# board.net
KiCad netlist of a schematic drawn in EAGLE
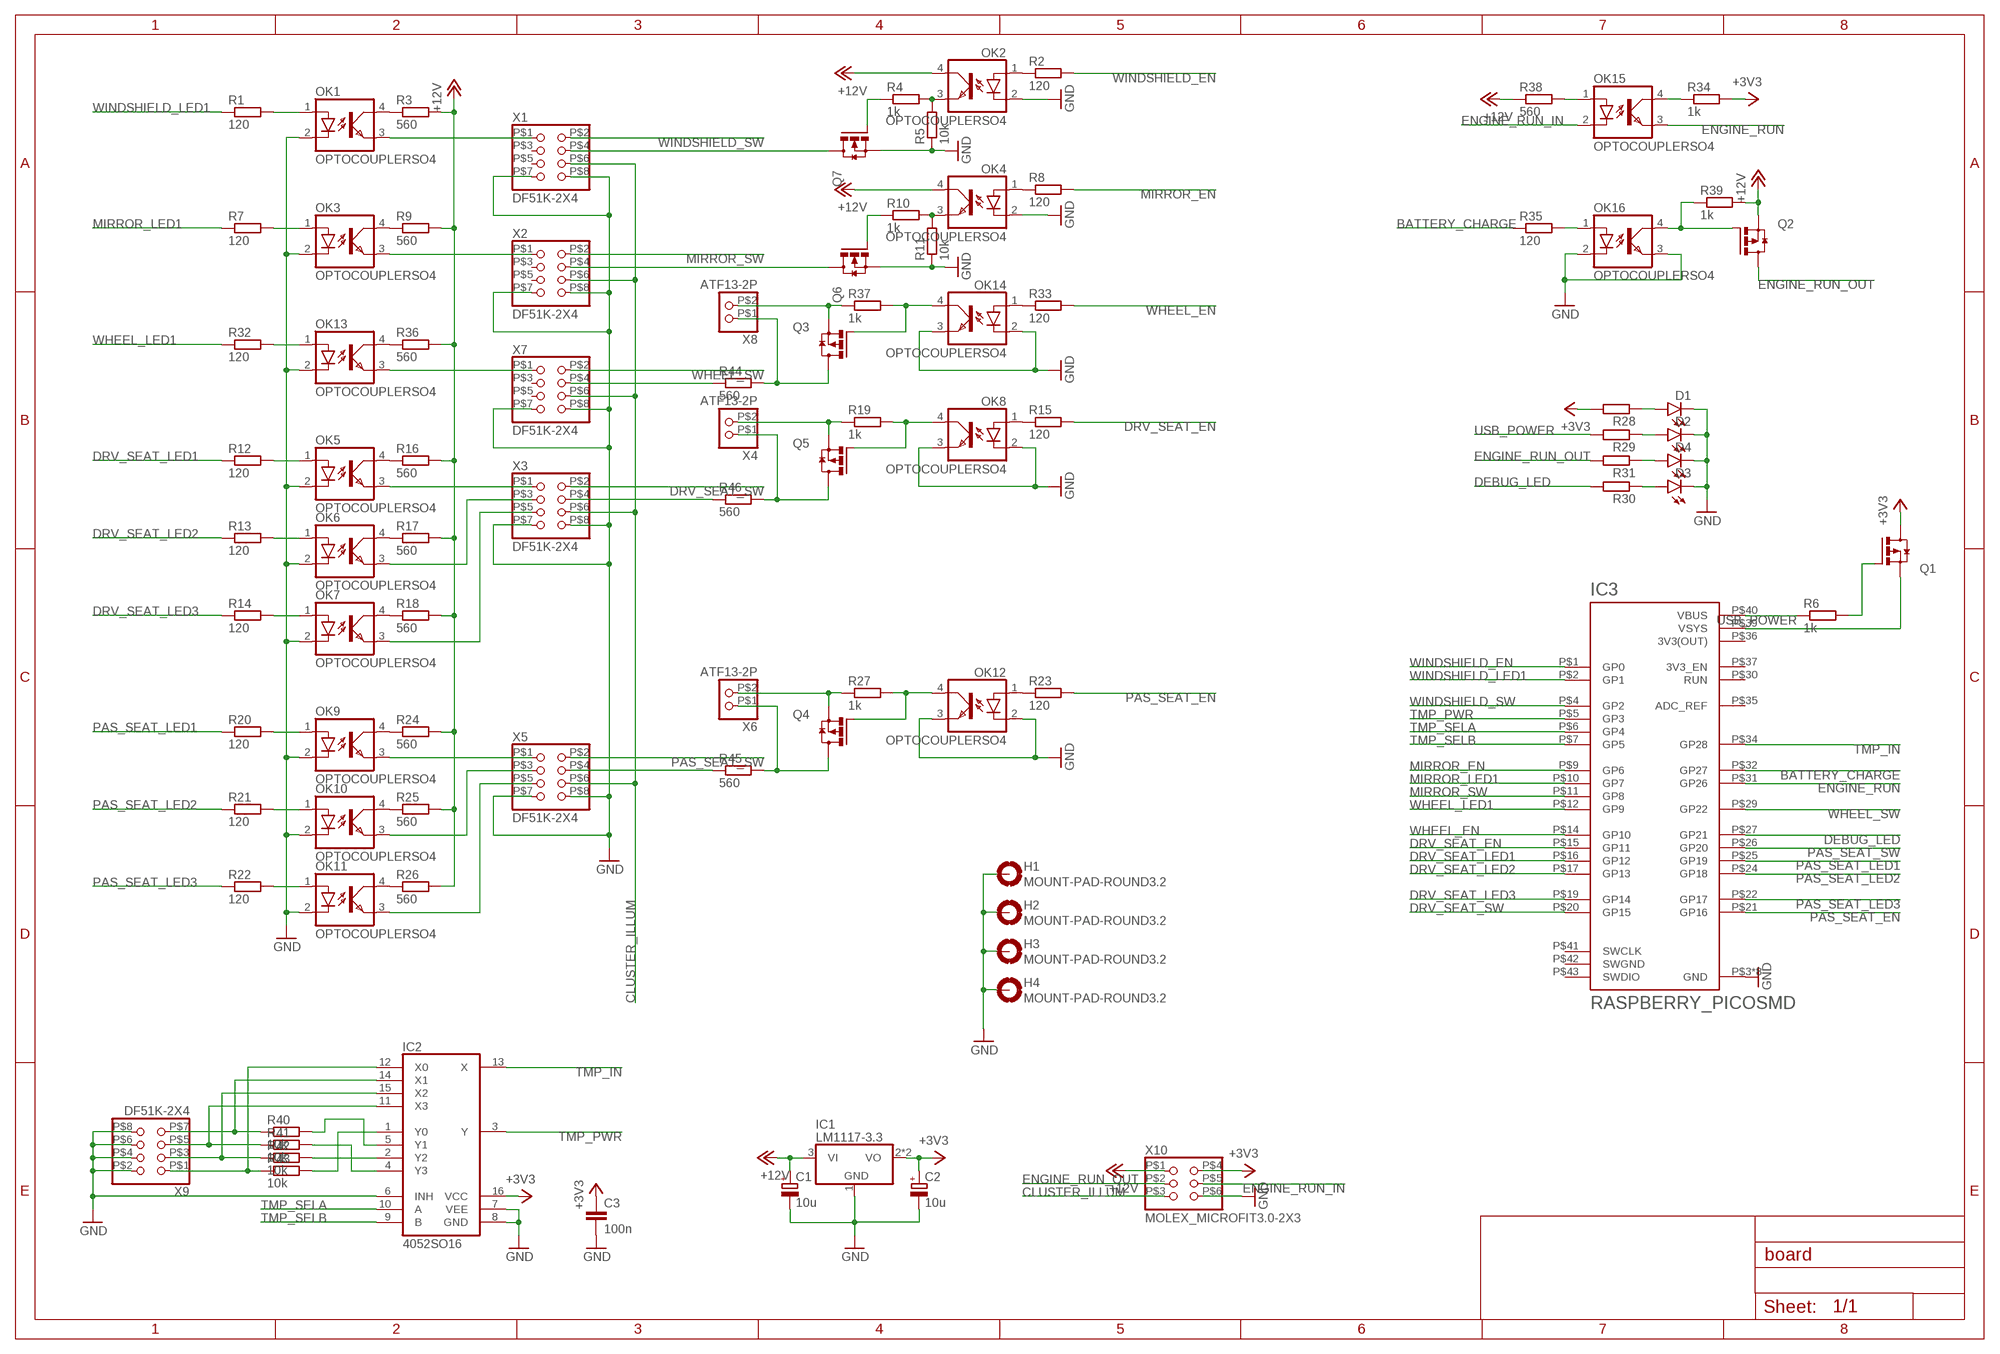
[diagram p0: schematic, sheet 1]

(export (version "E")
  (design (tool "Eeschema 10.0.6"))
  (components
    (comp (ref "C1")
      (value "10u")
      (footprint "eagle-import:C_4MM")
      (libsource (lib "eagle-import") (part "CAPACITOR_POL4MM^2"))
    )
    (comp (ref "C2")
      (value "10u")
      (footprint "eagle-import:C_4MM")
      (libsource (lib "eagle-import") (part "CAPACITOR_POL4MM^2"))
    )
    (comp (ref "C3")
      (value "100n")
      (footprint "eagle-import:C0805")
      (libsource (lib "eagle-import") (part "CAPACITOR0805"))
    )
    (comp (ref "D1")
      (value "LED1206")
      (footprint "eagle-import:CHIPLED_1206")
      (libsource (lib "eagle-import") (part "LED1206"))
    )
    (comp (ref "D2")
      (value "LED1206")
      (footprint "eagle-import:CHIPLED_1206")
      (libsource (lib "eagle-import") (part "LED1206"))
    )
    (comp (ref "D3")
      (value "LED1206")
      (footprint "eagle-import:CHIPLED_1206")
      (libsource (lib "eagle-import") (part "LED1206"))
    )
    (comp (ref "D4")
      (value "LED1206")
      (footprint "eagle-import:CHIPLED_1206")
      (libsource (lib "eagle-import") (part "LED1206"))
    )
    (comp (ref "H1")
      (value "MOUNT-PAD-ROUND3.2")
      (footprint "eagle-import:3,2-PAD")
      (libsource (lib "eagle-import") (part "MOUNT-PAD-ROUND3.2"))
    )
    (comp (ref "H2")
      (value "MOUNT-PAD-ROUND3.2")
      (footprint "eagle-import:3,2-PAD")
      (libsource (lib "eagle-import") (part "MOUNT-PAD-ROUND3.2"))
    )
    (comp (ref "H3")
      (value "MOUNT-PAD-ROUND3.2")
      (footprint "eagle-import:3,2-PAD")
      (libsource (lib "eagle-import") (part "MOUNT-PAD-ROUND3.2"))
    )
    (comp (ref "H4")
      (value "MOUNT-PAD-ROUND3.2")
      (footprint "eagle-import:3,2-PAD")
      (libsource (lib "eagle-import") (part "MOUNT-PAD-ROUND3.2"))
    )
    (comp (ref "IC1")
      (value "LM1117-3.3")
      (footprint "eagle-import:SOT223")
      (libsource (lib "eagle-import") (part "LM1117-3.3"))
    )
    (comp (ref "IC2")
      (value "4052SO16")
      (footprint "eagle-import:SO16")
      (libsource (lib "eagle-import") (part "4052SO16"))
    )
    (comp (ref "IC3")
      (value "RASPBERRY_PICOSMD")
      (footprint "eagle-import:PICO-PKG-SMD")
      (libsource (lib "eagle-import") (part "RASPBERRY_PICOSMD"))
    )
    (comp (ref "OK1")
      (value "OPTOCOUPLERSO4")
      (footprint "eagle-import:SO04")
      (libsource (lib "eagle-import") (part "OPTOCOUPLERSO4"))
    )
    (comp (ref "OK2")
      (value "OPTOCOUPLERSO4")
      (footprint "eagle-import:SO04")
      (libsource (lib "eagle-import") (part "OPTOCOUPLERSO4"))
    )
    (comp (ref "OK3")
      (value "OPTOCOUPLERSO4")
      (footprint "eagle-import:SO04")
      (libsource (lib "eagle-import") (part "OPTOCOUPLERSO4"))
    )
    (comp (ref "OK4")
      (value "OPTOCOUPLERSO4")
      (footprint "eagle-import:SO04")
      (libsource (lib "eagle-import") (part "OPTOCOUPLERSO4"))
    )
    (comp (ref "OK5")
      (value "OPTOCOUPLERSO4")
      (footprint "eagle-import:SO04")
      (libsource (lib "eagle-import") (part "OPTOCOUPLERSO4"))
    )
    (comp (ref "OK6")
      (value "OPTOCOUPLERSO4")
      (footprint "eagle-import:SO04")
      (libsource (lib "eagle-import") (part "OPTOCOUPLERSO4"))
    )
    (comp (ref "OK7")
      (value "OPTOCOUPLERSO4")
      (footprint "eagle-import:SO04")
      (libsource (lib "eagle-import") (part "OPTOCOUPLERSO4"))
    )
    (comp (ref "OK8")
      (value "OPTOCOUPLERSO4")
      (footprint "eagle-import:SO04")
      (libsource (lib "eagle-import") (part "OPTOCOUPLERSO4"))
    )
    (comp (ref "OK9")
      (value "OPTOCOUPLERSO4")
      (footprint "eagle-import:SO04")
      (libsource (lib "eagle-import") (part "OPTOCOUPLERSO4"))
    )
    (comp (ref "OK10")
      (value "OPTOCOUPLERSO4")
      (footprint "eagle-import:SO04")
      (libsource (lib "eagle-import") (part "OPTOCOUPLERSO4"))
    )
    (comp (ref "OK11")
      (value "OPTOCOUPLERSO4")
      (footprint "eagle-import:SO04")
      (libsource (lib "eagle-import") (part "OPTOCOUPLERSO4"))
    )
    (comp (ref "OK12")
      (value "OPTOCOUPLERSO4")
      (footprint "eagle-import:SO04")
      (libsource (lib "eagle-import") (part "OPTOCOUPLERSO4"))
    )
    (comp (ref "OK13")
      (value "OPTOCOUPLERSO4")
      (footprint "eagle-import:SO04")
      (libsource (lib "eagle-import") (part "OPTOCOUPLERSO4"))
    )
    (comp (ref "OK14")
      (value "OPTOCOUPLERSO4")
      (footprint "eagle-import:SO04")
      (libsource (lib "eagle-import") (part "OPTOCOUPLERSO4"))
    )
    (comp (ref "OK15")
      (value "OPTOCOUPLERSO4")
      (footprint "eagle-import:SO04")
      (libsource (lib "eagle-import") (part "OPTOCOUPLERSO4"))
    )
    (comp (ref "OK16")
      (value "OPTOCOUPLERSO4")
      (footprint "eagle-import:SO04")
      (libsource (lib "eagle-import") (part "OPTOCOUPLERSO4"))
    )
    (comp (ref "Q1")
      (value "MOSFET_P_CHANNELSOT23")
      (footprint "eagle-import:SOT23")
      (libsource (lib "eagle-import") (part "MOSFET_P_CHANNELSOT23"))
    )
    (comp (ref "Q2")
      (value "MOSFET_P_CHANNELSOT23")
      (footprint "eagle-import:SOT23")
      (libsource (lib "eagle-import") (part "MOSFET_P_CHANNELSOT23"))
    )
    (comp (ref "Q3")
      (value "MOSFET_P_CHANNELTO252")
      (footprint "eagle-import:TO252")
      (libsource (lib "eagle-import") (part "MOSFET_P_CHANNELTO252"))
    )
    (comp (ref "Q4")
      (value "MOSFET_P_CHANNELTO252")
      (footprint "eagle-import:TO252")
      (libsource (lib "eagle-import") (part "MOSFET_P_CHANNELTO252"))
    )
    (comp (ref "Q5")
      (value "MOSFET_P_CHANNELTO252")
      (footprint "eagle-import:TO252")
      (libsource (lib "eagle-import") (part "MOSFET_P_CHANNELTO252"))
    )
    (comp (ref "Q6")
      (value "MOSFET_N_CHANNELSOT23")
      (footprint "eagle-import:SOT23")
      (libsource (lib "eagle-import") (part "MOSFET_N_CHANNELSOT23"))
    )
    (comp (ref "Q7")
      (value "MOSFET_N_CHANNELSOT23")
      (footprint "eagle-import:SOT23")
      (libsource (lib "eagle-import") (part "MOSFET_N_CHANNELSOT23"))
    )
    (comp (ref "R1")
      (value "120")
      (footprint "eagle-import:R0805")
      (libsource (lib "eagle-import") (part "RESISTOR0805"))
    )
    (comp (ref "R2")
      (value "120")
      (footprint "eagle-import:R0805")
      (libsource (lib "eagle-import") (part "RESISTOR0805"))
    )
    (comp (ref "R3")
      (value "560")
      (footprint "eagle-import:R0805")
      (libsource (lib "eagle-import") (part "RESISTOR0805"))
    )
    (comp (ref "R4")
      (value "1k")
      (footprint "eagle-import:R0805")
      (libsource (lib "eagle-import") (part "RESISTOR0805"))
    )
    (comp (ref "R5")
      (value "10k")
      (footprint "eagle-import:R0805")
      (libsource (lib "eagle-import") (part "RESISTOR0805"))
    )
    (comp (ref "R6")
      (value "1k")
      (footprint "eagle-import:R0805")
      (libsource (lib "eagle-import") (part "RESISTOR0805"))
    )
    (comp (ref "R7")
      (value "120")
      (footprint "eagle-import:R0805")
      (libsource (lib "eagle-import") (part "RESISTOR0805"))
    )
    (comp (ref "R8")
      (value "120")
      (footprint "eagle-import:R0805")
      (libsource (lib "eagle-import") (part "RESISTOR0805"))
    )
    (comp (ref "R9")
      (value "560")
      (footprint "eagle-import:R0805")
      (libsource (lib "eagle-import") (part "RESISTOR0805"))
    )
    (comp (ref "R10")
      (value "1k")
      (footprint "eagle-import:R0805")
      (libsource (lib "eagle-import") (part "RESISTOR0805"))
    )
    (comp (ref "R11")
      (value "10k")
      (footprint "eagle-import:R0805")
      (libsource (lib "eagle-import") (part "RESISTOR0805"))
    )
    (comp (ref "R12")
      (value "120")
      (footprint "eagle-import:R0805")
      (libsource (lib "eagle-import") (part "RESISTOR0805"))
    )
    (comp (ref "R13")
      (value "120")
      (footprint "eagle-import:R0805")
      (libsource (lib "eagle-import") (part "RESISTOR0805"))
    )
    (comp (ref "R14")
      (value "120")
      (footprint "eagle-import:R0805")
      (libsource (lib "eagle-import") (part "RESISTOR0805"))
    )
    (comp (ref "R15")
      (value "120")
      (footprint "eagle-import:R0805")
      (libsource (lib "eagle-import") (part "RESISTOR0805"))
    )
    (comp (ref "R16")
      (value "560")
      (footprint "eagle-import:R0805")
      (libsource (lib "eagle-import") (part "RESISTOR0805"))
    )
    (comp (ref "R17")
      (value "560")
      (footprint "eagle-import:R0805")
      (libsource (lib "eagle-import") (part "RESISTOR0805"))
    )
    (comp (ref "R18")
      (value "560")
      (footprint "eagle-import:R0805")
      (libsource (lib "eagle-import") (part "RESISTOR0805"))
    )
    (comp (ref "R19")
      (value "1k")
      (footprint "eagle-import:R0805")
      (libsource (lib "eagle-import") (part "RESISTOR0805"))
    )
    (comp (ref "R20")
      (value "120")
      (footprint "eagle-import:R0805")
      (libsource (lib "eagle-import") (part "RESISTOR0805"))
    )
    (comp (ref "R21")
      (value "120")
      (footprint "eagle-import:R0805")
      (libsource (lib "eagle-import") (part "RESISTOR0805"))
    )
    (comp (ref "R22")
      (value "120")
      (footprint "eagle-import:R0805")
      (libsource (lib "eagle-import") (part "RESISTOR0805"))
    )
    (comp (ref "R23")
      (value "120")
      (footprint "eagle-import:R0805")
      (libsource (lib "eagle-import") (part "RESISTOR0805"))
    )
    (comp (ref "R24")
      (value "560")
      (footprint "eagle-import:R0805")
      (libsource (lib "eagle-import") (part "RESISTOR0805"))
    )
    (comp (ref "R25")
      (value "560")
      (footprint "eagle-import:R0805")
      (libsource (lib "eagle-import") (part "RESISTOR0805"))
    )
    (comp (ref "R26")
      (value "560")
      (footprint "eagle-import:R0805")
      (libsource (lib "eagle-import") (part "RESISTOR0805"))
    )
    (comp (ref "R27")
      (value "1k")
      (footprint "eagle-import:R0805")
      (libsource (lib "eagle-import") (part "RESISTOR0805"))
    )
    (comp (ref "R28")
      (value "RESISTOR0805")
      (footprint "eagle-import:R0805")
      (libsource (lib "eagle-import") (part "RESISTOR0805"))
    )
    (comp (ref "R29")
      (value "RESISTOR0805")
      (footprint "eagle-import:R0805")
      (libsource (lib "eagle-import") (part "RESISTOR0805"))
    )
    (comp (ref "R30")
      (value "RESISTOR0805")
      (footprint "eagle-import:R0805")
      (libsource (lib "eagle-import") (part "RESISTOR0805"))
    )
    (comp (ref "R31")
      (value "RESISTOR0805")
      (footprint "eagle-import:R0805")
      (libsource (lib "eagle-import") (part "RESISTOR0805"))
    )
    (comp (ref "R32")
      (value "120")
      (footprint "eagle-import:R0805")
      (libsource (lib "eagle-import") (part "RESISTOR0805"))
    )
    (comp (ref "R33")
      (value "120")
      (footprint "eagle-import:R0805")
      (libsource (lib "eagle-import") (part "RESISTOR0805"))
    )
    (comp (ref "R34")
      (value "1k")
      (footprint "eagle-import:R0805")
      (libsource (lib "eagle-import") (part "RESISTOR0805"))
    )
    (comp (ref "R35")
      (value "120")
      (footprint "eagle-import:R0805")
      (libsource (lib "eagle-import") (part "RESISTOR0805"))
    )
    (comp (ref "R36")
      (value "560")
      (footprint "eagle-import:R0805")
      (libsource (lib "eagle-import") (part "RESISTOR0805"))
    )
    (comp (ref "R37")
      (value "1k")
      (footprint "eagle-import:R0805")
      (libsource (lib "eagle-import") (part "RESISTOR0805"))
    )
    (comp (ref "R38")
      (value "560")
      (footprint "eagle-import:R0805")
      (libsource (lib "eagle-import") (part "RESISTOR0805"))
    )
    (comp (ref "R39")
      (value "1k")
      (footprint "eagle-import:R0805")
      (libsource (lib "eagle-import") (part "RESISTOR0805"))
    )
    (comp (ref "R40")
      (value "10k")
      (footprint "eagle-import:R0805")
      (libsource (lib "eagle-import") (part "RESISTOR0805"))
    )
    (comp (ref "R41")
      (value "10k")
      (footprint "eagle-import:R0805")
      (libsource (lib "eagle-import") (part "RESISTOR0805"))
    )
    (comp (ref "R42")
      (value "10k")
      (footprint "eagle-import:R0805")
      (libsource (lib "eagle-import") (part "RESISTOR0805"))
    )
    (comp (ref "R43")
      (value "10k")
      (footprint "eagle-import:R0805")
      (libsource (lib "eagle-import") (part "RESISTOR0805"))
    )
    (comp (ref "R44")
      (value "560")
      (footprint "eagle-import:R0805")
      (libsource (lib "eagle-import") (part "RESISTOR0805"))
    )
    (comp (ref "R45")
      (value "560")
      (footprint "eagle-import:R0805")
      (libsource (lib "eagle-import") (part "RESISTOR0805"))
    )
    (comp (ref "R46")
      (value "560")
      (footprint "eagle-import:R0805")
      (libsource (lib "eagle-import") (part "RESISTOR0805"))
    )
    (comp (ref "X1")
      (value "DF51K-2X4")
      (footprint "eagle-import:DF51K-2X4")
      (libsource (lib "eagle-import") (part "DF51K-2X4"))
    )
    (comp (ref "X2")
      (value "DF51K-2X4")
      (footprint "eagle-import:DF51K-2X4")
      (libsource (lib "eagle-import") (part "DF51K-2X4"))
    )
    (comp (ref "X3")
      (value "DF51K-2X4")
      (footprint "eagle-import:DF51K-2X4")
      (libsource (lib "eagle-import") (part "DF51K-2X4"))
    )
    (comp (ref "X4")
      (value "ATF13-2P")
      (footprint "eagle-import:ATF13-2P")
      (libsource (lib "eagle-import") (part "ATF13-2P"))
    )
    (comp (ref "X5")
      (value "DF51K-2X4")
      (footprint "eagle-import:DF51K-2X4")
      (libsource (lib "eagle-import") (part "DF51K-2X4"))
    )
    (comp (ref "X6")
      (value "ATF13-2P")
      (footprint "eagle-import:ATF13-2P")
      (libsource (lib "eagle-import") (part "ATF13-2P"))
    )
    (comp (ref "X7")
      (value "DF51K-2X4")
      (footprint "eagle-import:DF51K-2X4")
      (libsource (lib "eagle-import") (part "DF51K-2X4"))
    )
    (comp (ref "X8")
      (value "ATF13-2P")
      (footprint "eagle-import:ATF13-2P")
      (libsource (lib "eagle-import") (part "ATF13-2P"))
    )
    (comp (ref "X9")
      (value "DF51K-2X4")
      (footprint "eagle-import:DF51K-2X4")
      (libsource (lib "eagle-import") (part "DF51K-2X4"))
    )
    (comp (ref "X10")
      (value "MOLEX_MICROFIT3.0-2X3")
      (footprint "eagle-import:MOLEX_MICROFIT3.0-2X3")
      (libsource (lib "eagle-import") (part "MOLEX_MICROFIT3.0-2X3"))
    )
  )
  (nets
    (net (code "1") (name "+3V3") (class "Default")
      (node (ref "C2") (pin "+") (pinfunction "+_+") (pintype "passive"))
      (node (ref "C3") (pin "1") (pinfunction "1_1") (pintype "passive"))
      (node (ref "IC1") (pin "2") (pinfunction "VO_2") (pintype "passive"))
      (node (ref "IC1") (pin "4") (pinfunction "VO_4") (pintype "passive"))
      (node (ref "IC2") (pin "16") (pinfunction "VCC_16") (pintype "bidirectional"))
      (node (ref "Q1") (pin "3") (pinfunction "D_3") (pintype "passive"))
      (node (ref "R28") (pin "2") (pinfunction "2_2") (pintype "passive"))
      (node (ref "R34") (pin "2") (pinfunction "2_2") (pintype "passive"))
      (node (ref "X10") (pin "P$4") (pinfunction "2_P$4") (pintype "passive"))
    )
    (net (code "2") (name "+12V") (class "Default")
      (node (ref "C1") (pin "+") (pinfunction "+_+") (pintype "passive"))
      (node (ref "IC1") (pin "3") (pinfunction "VI_3") (pintype "input"))
      (node (ref "OK2") (pin "4") (pinfunction "COL_4") (pintype "passive"))
      (node (ref "OK4") (pin "4") (pinfunction "COL_4") (pintype "passive"))
      (node (ref "Q2") (pin "2") (pinfunction "S_2") (pintype "passive"))
      (node (ref "R16") (pin "2") (pinfunction "2_2") (pintype "passive"))
      (node (ref "R17") (pin "2") (pinfunction "2_2") (pintype "passive"))
      (node (ref "R18") (pin "2") (pinfunction "2_2") (pintype "passive"))
      (node (ref "R24") (pin "2") (pinfunction "2_2") (pintype "passive"))
      (node (ref "R25") (pin "2") (pinfunction "2_2") (pintype "passive"))
      (node (ref "R26") (pin "2") (pinfunction "2_2") (pintype "passive"))
      (node (ref "R3") (pin "2") (pinfunction "2_2") (pintype "passive"))
      (node (ref "R36") (pin "2") (pinfunction "2_2") (pintype "passive"))
      (node (ref "R38") (pin "1") (pinfunction "1_1") (pintype "passive"))
      (node (ref "R39") (pin "2") (pinfunction "2_2") (pintype "passive"))
      (node (ref "R9") (pin "2") (pinfunction "2_2") (pintype "passive"))
      (node (ref "X10") (pin "P$1") (pinfunction "1_P$1") (pintype "passive"))
    )
    (net (code "3") (name "/3V3(OUT)") (class "Default")
      (node (ref "IC3") (pin "P$36") (pinfunction "3V3(OUT)_P$36") (pintype "power_in"))
    )
    (net (code "4") (name "/BATTERY_CHARGE") (class "Default")
      (node (ref "IC3") (pin "P$32") (pinfunction "GP27_P$32") (pintype "bidirectional"))
      (node (ref "R35") (pin "1") (pinfunction "1_1") (pintype "passive"))
    )
    (net (code "5") (name "/CLUSTER_ILLUM") (class "Default")
      (node (ref "X1") (pin "P$6") (pinfunction "6_P$6") (pintype "passive"))
      (node (ref "X10") (pin "P$3") (pinfunction "5_P$3") (pintype "passive"))
      (node (ref "X2") (pin "P$6") (pinfunction "6_P$6") (pintype "passive"))
      (node (ref "X3") (pin "P$6") (pinfunction "6_P$6") (pintype "passive"))
      (node (ref "X5") (pin "P$6") (pinfunction "6_P$6") (pintype "passive"))
      (node (ref "X7") (pin "P$6") (pinfunction "6_P$6") (pintype "passive"))
    )
    (net (code "6") (name "/DEBUG_LED") (class "Default")
      (node (ref "IC3") (pin "P$27") (pinfunction "GP21_P$27") (pintype "bidirectional"))
      (node (ref "R30") (pin "2") (pinfunction "2_2") (pintype "passive"))
    )
    (net (code "7") (name "/DRV_SEAT_EN") (class "Default")
      (node (ref "IC3") (pin "P$15") (pinfunction "GP11_P$15") (pintype "bidirectional"))
      (node (ref "R15") (pin "2") (pinfunction "2_2") (pintype "passive"))
    )
    (net (code "8") (name "/DRV_SEAT_LED1") (class "Default")
      (node (ref "IC3") (pin "P$16") (pinfunction "GP12_P$16") (pintype "bidirectional"))
      (node (ref "R12") (pin "1") (pinfunction "1_1") (pintype "passive"))
    )
    (net (code "9") (name "/DRV_SEAT_LED2") (class "Default")
      (node (ref "IC3") (pin "P$17") (pinfunction "GP13_P$17") (pintype "bidirectional"))
      (node (ref "R13") (pin "1") (pinfunction "1_1") (pintype "passive"))
    )
    (net (code "10") (name "/DRV_SEAT_LED3") (class "Default")
      (node (ref "IC3") (pin "P$19") (pinfunction "GP14_P$19") (pintype "bidirectional"))
      (node (ref "R14") (pin "1") (pinfunction "1_1") (pintype "passive"))
    )
    (net (code "11") (name "/DRV_SEAT_SW") (class "Default")
      (node (ref "IC3") (pin "P$20") (pinfunction "GP15_P$20") (pintype "bidirectional"))
      (node (ref "X3") (pin "P$2") (pinfunction "2_P$2") (pintype "passive"))
    )
    (net (code "12") (name "/ENGINE_RUN") (class "Default")
      (node (ref "IC3") (pin "P$31") (pinfunction "GP26_P$31") (pintype "bidirectional"))
      (node (ref "OK15") (pin "3") (pinfunction "EMIT_3") (pintype "passive"))
    )
    (net (code "13") (name "/ENGINE_RUN_IN") (class "Default")
      (node (ref "OK15") (pin "2") (pinfunction "C_2") (pintype "passive"))
      (node (ref "X10") (pin "P$5") (pinfunction "4_P$5") (pintype "passive"))
    )
    (net (code "14") (name "/ENGINE_RUN_OUT") (class "Default")
      (node (ref "Q2") (pin "3") (pinfunction "D_3") (pintype "passive"))
      (node (ref "R31") (pin "2") (pinfunction "2_2") (pintype "passive"))
      (node (ref "X10") (pin "P$2") (pinfunction "3_P$2") (pintype "passive"))
    )
    (net (code "15") (name "/MIRROR_EN") (class "Default")
      (node (ref "IC3") (pin "P$9") (pinfunction "GP6_P$9") (pintype "bidirectional"))
      (node (ref "R8") (pin "2") (pinfunction "2_2") (pintype "passive"))
    )
    (net (code "16") (name "/MIRROR_LED1") (class "Default")
      (node (ref "IC3") (pin "P$10") (pinfunction "GP7_P$10") (pintype "bidirectional"))
      (node (ref "R7") (pin "1") (pinfunction "1_1") (pintype "passive"))
    )
    (net (code "17") (name "/MIRROR_SW") (class "Default")
      (node (ref "IC3") (pin "P$11") (pinfunction "GP8_P$11") (pintype "bidirectional"))
      (node (ref "X2") (pin "P$2") (pinfunction "2_P$2") (pintype "passive"))
    )
    (net (code "18") (name "/PAS_SEAT_EN") (class "Default")
      (node (ref "IC3") (pin "P$21") (pinfunction "GP16_P$21") (pintype "bidirectional"))
      (node (ref "R23") (pin "2") (pinfunction "2_2") (pintype "passive"))
    )
    (net (code "19") (name "/PAS_SEAT_LED1") (class "Default")
      (node (ref "IC3") (pin "P$25") (pinfunction "GP19_P$25") (pintype "bidirectional"))
      (node (ref "R20") (pin "1") (pinfunction "1_1") (pintype "passive"))
    )
    (net (code "20") (name "/PAS_SEAT_LED2") (class "Default")
      (node (ref "IC3") (pin "P$24") (pinfunction "GP18_P$24") (pintype "bidirectional"))
      (node (ref "R21") (pin "1") (pinfunction "1_1") (pintype "passive"))
    )
    (net (code "21") (name "/PAS_SEAT_LED3") (class "Default")
      (node (ref "IC3") (pin "P$22") (pinfunction "GP17_P$22") (pintype "bidirectional"))
      (node (ref "R22") (pin "1") (pinfunction "1_1") (pintype "passive"))
    )
    (net (code "22") (name "/PAS_SEAT_SW") (class "Default")
      (node (ref "IC3") (pin "P$26") (pinfunction "GP20_P$26") (pintype "bidirectional"))
      (node (ref "X5") (pin "P$2") (pinfunction "2_P$2") (pintype "passive"))
    )
    (net (code "23") (name "/SWGND") (class "Default")
      (node (ref "IC3") (pin "P$42") (pinfunction "SWGND_P$42") (pintype "power_in"))
    )
    (net (code "24") (name "/TMP_IN") (class "Default")
      (node (ref "IC2") (pin "13") (pinfunction "X_13") (pintype "bidirectional"))
      (node (ref "IC3") (pin "P$34") (pinfunction "GP28_P$34") (pintype "bidirectional"))
    )
    (net (code "25") (name "/TMP_PWR") (class "Default")
      (node (ref "IC2") (pin "3") (pinfunction "Y_3") (pintype "bidirectional"))
      (node (ref "IC3") (pin "P$5") (pinfunction "GP3_P$5") (pintype "bidirectional"))
    )
    (net (code "26") (name "/TMP_SELA") (class "Default")
      (node (ref "IC2") (pin "10") (pinfunction "A_10") (pintype "input"))
      (node (ref "IC3") (pin "P$6") (pinfunction "GP4_P$6") (pintype "bidirectional"))
    )
    (net (code "27") (name "/TMP_SELB") (class "Default")
      (node (ref "IC2") (pin "9") (pinfunction "B_9") (pintype "input"))
      (node (ref "IC3") (pin "P$7") (pinfunction "GP5_P$7") (pintype "bidirectional"))
    )
    (net (code "28") (name "/USB_POWER") (class "Default")
      (node (ref "IC3") (pin "P$40") (pinfunction "VBUS_P$40") (pintype "power_in"))
      (node (ref "R29") (pin "2") (pinfunction "2_2") (pintype "passive"))
      (node (ref "R6") (pin "1") (pinfunction "1_1") (pintype "passive"))
    )
    (net (code "29") (name "/WHEEL_EN") (class "Default")
      (node (ref "IC3") (pin "P$14") (pinfunction "GP10_P$14") (pintype "bidirectional"))
      (node (ref "R33") (pin "2") (pinfunction "2_2") (pintype "passive"))
    )
    (net (code "30") (name "/WHEEL_LED1") (class "Default")
      (node (ref "IC3") (pin "P$12") (pinfunction "GP9_P$12") (pintype "bidirectional"))
      (node (ref "R32") (pin "1") (pinfunction "1_1") (pintype "passive"))
    )
    (net (code "31") (name "/WHEEL_SW") (class "Default")
      (node (ref "IC3") (pin "P$29") (pinfunction "GP22_P$29") (pintype "bidirectional"))
      (node (ref "X7") (pin "P$2") (pinfunction "2_P$2") (pintype "passive"))
    )
    (net (code "32") (name "/WINDSHIELD_EN") (class "Default")
      (node (ref "IC3") (pin "P$1") (pinfunction "GP0_P$1") (pintype "bidirectional"))
      (node (ref "R2") (pin "2") (pinfunction "2_2") (pintype "passive"))
    )
    (net (code "33") (name "/WINDSHIELD_LED1") (class "Default")
      (node (ref "IC3") (pin "P$2") (pinfunction "GP1_P$2") (pintype "bidirectional"))
      (node (ref "R1") (pin "1") (pinfunction "1_1") (pintype "passive"))
    )
    (net (code "34") (name "/WINDSHIELD_SW") (class "Default")
      (node (ref "IC3") (pin "P$4") (pinfunction "GP2_P$4") (pintype "bidirectional"))
      (node (ref "X1") (pin "P$2") (pinfunction "2_P$2") (pintype "passive"))
    )
    (net (code "35") (name "GND") (class "Default")
      (node (ref "C1") (pin "-") (pinfunction "-_-") (pintype "passive"))
      (node (ref "C2") (pin "-") (pinfunction "-_-") (pintype "passive"))
      (node (ref "C3") (pin "2") (pinfunction "2_2") (pintype "passive"))
      (node (ref "D1") (pin "C") (pinfunction "C_C") (pintype "passive"))
      (node (ref "D2") (pin "C") (pinfunction "C_C") (pintype "passive"))
      (node (ref "D3") (pin "C") (pinfunction "C_C") (pintype "passive"))
      (node (ref "D4") (pin "C") (pinfunction "C_C") (pintype "passive"))
      (node (ref "H1") (pin "B3,2") (pinfunction "MOUNT_B3,2") (pintype "passive"))
      (node (ref "H1") (pin "P$1") (pinfunction "MOUNT_P$1") (pintype "passive"))
      (node (ref "H1") (pin "P$2") (pinfunction "MOUNT_P$2") (pintype "passive"))
      (node (ref "H1") (pin "P$3") (pinfunction "MOUNT_P$3") (pintype "passive"))
      (node (ref "H1") (pin "P$4") (pinfunction "MOUNT_P$4") (pintype "passive"))
      (node (ref "H1") (pin "P$5") (pinfunction "MOUNT_P$5") (pintype "passive"))
      (node (ref "H1") (pin "P$6") (pinfunction "MOUNT_P$6") (pintype "passive"))
      (node (ref "H1") (pin "P$7") (pinfunction "MOUNT_P$7") (pintype "passive"))
      (node (ref "H1") (pin "P$8") (pinfunction "MOUNT_P$8") (pintype "passive"))
      (node (ref "H2") (pin "B3,2") (pinfunction "MOUNT_B3,2") (pintype "passive"))
      (node (ref "H2") (pin "P$1") (pinfunction "MOUNT_P$1") (pintype "passive"))
      (node (ref "H2") (pin "P$2") (pinfunction "MOUNT_P$2") (pintype "passive"))
      (node (ref "H2") (pin "P$3") (pinfunction "MOUNT_P$3") (pintype "passive"))
      (node (ref "H2") (pin "P$4") (pinfunction "MOUNT_P$4") (pintype "passive"))
      (node (ref "H2") (pin "P$5") (pinfunction "MOUNT_P$5") (pintype "passive"))
      (node (ref "H2") (pin "P$6") (pinfunction "MOUNT_P$6") (pintype "passive"))
      (node (ref "H2") (pin "P$7") (pinfunction "MOUNT_P$7") (pintype "passive"))
      (node (ref "H2") (pin "P$8") (pinfunction "MOUNT_P$8") (pintype "passive"))
      (node (ref "H3") (pin "B3,2") (pinfunction "MOUNT_B3,2") (pintype "passive"))
      (node (ref "H3") (pin "P$1") (pinfunction "MOUNT_P$1") (pintype "passive"))
      (node (ref "H3") (pin "P$2") (pinfunction "MOUNT_P$2") (pintype "passive"))
      (node (ref "H3") (pin "P$3") (pinfunction "MOUNT_P$3") (pintype "passive"))
      (node (ref "H3") (pin "P$4") (pinfunction "MOUNT_P$4") (pintype "passive"))
      (node (ref "H3") (pin "P$5") (pinfunction "MOUNT_P$5") (pintype "passive"))
      (node (ref "H3") (pin "P$6") (pinfunction "MOUNT_P$6") (pintype "passive"))
      (node (ref "H3") (pin "P$7") (pinfunction "MOUNT_P$7") (pintype "passive"))
      (node (ref "H3") (pin "P$8") (pinfunction "MOUNT_P$8") (pintype "passive"))
      (node (ref "H4") (pin "B3,2") (pinfunction "MOUNT_B3,2") (pintype "passive"))
      (node (ref "H4") (pin "P$1") (pinfunction "MOUNT_P$1") (pintype "passive"))
      (node (ref "H4") (pin "P$2") (pinfunction "MOUNT_P$2") (pintype "passive"))
      (node (ref "H4") (pin "P$3") (pinfunction "MOUNT_P$3") (pintype "passive"))
      (node (ref "H4") (pin "P$4") (pinfunction "MOUNT_P$4") (pintype "passive"))
      (node (ref "H4") (pin "P$5") (pinfunction "MOUNT_P$5") (pintype "passive"))
      (node (ref "H4") (pin "P$6") (pinfunction "MOUNT_P$6") (pintype "passive"))
      (node (ref "H4") (pin "P$7") (pinfunction "MOUNT_P$7") (pintype "passive"))
      (node (ref "H4") (pin "P$8") (pinfunction "MOUNT_P$8") (pintype "passive"))
      (node (ref "IC1") (pin "1") (pinfunction "GND_1") (pintype "passive"))
      (node (ref "IC2") (pin "6") (pinfunction "INH_6") (pintype "input"))
      (node (ref "IC2") (pin "7") (pinfunction "VEE_7") (pintype "bidirectional"))
      (node (ref "IC2") (pin "8") (pinfunction "GND_8") (pintype "bidirectional"))
      (node (ref "IC3") (pin "P$13") (pinfunction "GND_P$13") (pintype "power_in"))
      (node (ref "IC3") (pin "P$18") (pinfunction "GND_P$18") (pintype "power_in"))
      (node (ref "IC3") (pin "P$23") (pinfunction "GND_P$23") (pintype "power_in"))
      (node (ref "IC3") (pin "P$28") (pinfunction "GND_P$28") (pintype "power_in"))
      (node (ref "IC3") (pin "P$3") (pinfunction "GND_P$3") (pintype "power_in"))
      (node (ref "IC3") (pin "P$33") (pinfunction "GND_P$33") (pintype "power_in"))
      (node (ref "IC3") (pin "P$38") (pinfunction "GND_P$38") (pintype "power_in"))
      (node (ref "IC3") (pin "P$8") (pinfunction "GND_P$8") (pintype "power_in"))
      (node (ref "OK1") (pin "2") (pinfunction "C_2") (pintype "passive"))
      (node (ref "OK10") (pin "2") (pinfunction "C_2") (pintype "passive"))
      (node (ref "OK11") (pin "2") (pinfunction "C_2") (pintype "passive"))
      (node (ref "OK12") (pin "2") (pinfunction "C_2") (pintype "passive"))
      (node (ref "OK12") (pin "3") (pinfunction "EMIT_3") (pintype "passive"))
      (node (ref "OK13") (pin "2") (pinfunction "C_2") (pintype "passive"))
      (node (ref "OK14") (pin "2") (pinfunction "C_2") (pintype "passive"))
      (node (ref "OK14") (pin "3") (pinfunction "EMIT_3") (pintype "passive"))
      (node (ref "OK16") (pin "2") (pinfunction "C_2") (pintype "passive"))
      (node (ref "OK16") (pin "3") (pinfunction "EMIT_3") (pintype "passive"))
      (node (ref "OK2") (pin "2") (pinfunction "C_2") (pintype "passive"))
      (node (ref "OK3") (pin "2") (pinfunction "C_2") (pintype "passive"))
      (node (ref "OK4") (pin "2") (pinfunction "C_2") (pintype "passive"))
      (node (ref "OK5") (pin "2") (pinfunction "C_2") (pintype "passive"))
      (node (ref "OK6") (pin "2") (pinfunction "C_2") (pintype "passive"))
      (node (ref "OK7") (pin "2") (pinfunction "C_2") (pintype "passive"))
      (node (ref "OK8") (pin "2") (pinfunction "C_2") (pintype "passive"))
      (node (ref "OK8") (pin "3") (pinfunction "EMIT_3") (pintype "passive"))
      (node (ref "OK9") (pin "2") (pinfunction "C_2") (pintype "passive"))
      (node (ref "Q6") (pin "2") (pinfunction "S_2") (pintype "passive"))
      (node (ref "Q7") (pin "2") (pinfunction "S_2") (pintype "passive"))
      (node (ref "R11") (pin "1") (pinfunction "1_1") (pintype "passive"))
      (node (ref "R5") (pin "1") (pinfunction "1_1") (pintype "passive"))
      (node (ref "X1") (pin "P$7") (pinfunction "7_P$7") (pintype "passive"))
      (node (ref "X1") (pin "P$8") (pinfunction "8_P$8") (pintype "passive"))
      (node (ref "X10") (pin "P$6") (pinfunction "6_P$6") (pintype "passive"))
      (node (ref "X2") (pin "P$7") (pinfunction "7_P$7") (pintype "passive"))
      (node (ref "X2") (pin "P$8") (pinfunction "8_P$8") (pintype "passive"))
      (node (ref "X3") (pin "P$7") (pinfunction "7_P$7") (pintype "passive"))
      (node (ref "X3") (pin "P$8") (pinfunction "8_P$8") (pintype "passive"))
      (node (ref "X5") (pin "P$7") (pinfunction "7_P$7") (pintype "passive"))
      (node (ref "X5") (pin "P$8") (pinfunction "8_P$8") (pintype "passive"))
      (node (ref "X7") (pin "P$7") (pinfunction "7_P$7") (pintype "passive"))
      (node (ref "X7") (pin "P$8") (pinfunction "8_P$8") (pintype "passive"))
      (node (ref "X9") (pin "P$2") (pinfunction "2_P$2") (pintype "passive"))
      (node (ref "X9") (pin "P$4") (pinfunction "4_P$4") (pintype "passive"))
      (node (ref "X9") (pin "P$6") (pinfunction "6_P$6") (pintype "passive"))
      (node (ref "X9") (pin "P$8") (pinfunction "8_P$8") (pintype "passive"))
    )
    (net (code "36") (name "Net-(D1-PadA)") (class "Default")
      (node (ref "D1") (pin "A") (pinfunction "A_A") (pintype "passive"))
      (node (ref "R28") (pin "1") (pinfunction "1_1") (pintype "passive"))
    )
    (net (code "37") (name "Net-(D2-PadA)") (class "Default")
      (node (ref "D2") (pin "A") (pinfunction "A_A") (pintype "passive"))
      (node (ref "R29") (pin "1") (pinfunction "1_1") (pintype "passive"))
    )
    (net (code "38") (name "Net-(D3-PadA)") (class "Default")
      (node (ref "D3") (pin "A") (pinfunction "A_A") (pintype "passive"))
      (node (ref "R30") (pin "1") (pinfunction "1_1") (pintype "passive"))
    )
    (net (code "39") (name "Net-(D4-PadA)") (class "Default")
      (node (ref "D4") (pin "A") (pinfunction "A_A") (pintype "passive"))
      (node (ref "R31") (pin "1") (pinfunction "1_1") (pintype "passive"))
    )
    (net (code "40") (name "Net-(IC2-X0)") (class "Default")
      (node (ref "IC2") (pin "12") (pinfunction "X0_12") (pintype "bidirectional"))
      (node (ref "R43") (pin "1") (pinfunction "1_1") (pintype "passive"))
      (node (ref "X9") (pin "P$1") (pinfunction "1_P$1") (pintype "passive"))
    )
    (net (code "41") (name "Net-(IC2-X1)") (class "Default")
      (node (ref "IC2") (pin "14") (pinfunction "X1_14") (pintype "bidirectional"))
      (node (ref "R40") (pin "1") (pinfunction "1_1") (pintype "passive"))
      (node (ref "X9") (pin "P$7") (pinfunction "7_P$7") (pintype "passive"))
    )
    (net (code "42") (name "Net-(IC2-X2)") (class "Default")
      (node (ref "IC2") (pin "15") (pinfunction "X2_15") (pintype "bidirectional"))
      (node (ref "R42") (pin "1") (pinfunction "1_1") (pintype "passive"))
      (node (ref "X9") (pin "P$3") (pinfunction "3_P$3") (pintype "passive"))
    )
    (net (code "43") (name "Net-(IC2-X3)") (class "Default")
      (node (ref "IC2") (pin "11") (pinfunction "X3_11") (pintype "bidirectional"))
      (node (ref "R41") (pin "1") (pinfunction "1_1") (pintype "passive"))
      (node (ref "X9") (pin "P$5") (pinfunction "5_P$5") (pintype "passive"))
    )
    (net (code "44") (name "Net-(IC2-Y0)") (class "Default")
      (node (ref "IC2") (pin "1") (pinfunction "Y0_1") (pintype "bidirectional"))
      (node (ref "R43") (pin "2") (pinfunction "2_2") (pintype "passive"))
    )
    (net (code "45") (name "Net-(IC2-Y1)") (class "Default")
      (node (ref "IC2") (pin "5") (pinfunction "Y1_5") (pintype "bidirectional"))
      (node (ref "R40") (pin "2") (pinfunction "2_2") (pintype "passive"))
    )
    (net (code "46") (name "Net-(IC2-Y2)") (class "Default")
      (node (ref "IC2") (pin "2") (pinfunction "Y2_2") (pintype "bidirectional"))
      (node (ref "R42") (pin "2") (pinfunction "2_2") (pintype "passive"))
    )
    (net (code "47") (name "Net-(IC2-Y3)") (class "Default")
      (node (ref "IC2") (pin "4") (pinfunction "Y3_4") (pintype "bidirectional"))
      (node (ref "R41") (pin "2") (pinfunction "2_2") (pintype "passive"))
    )
    (net (code "48") (name "Net-(IC3-VSYS)") (class "Default")
      (node (ref "IC3") (pin "P$39") (pinfunction "VSYS_P$39") (pintype "power_in"))
      (node (ref "Q1") (pin "2") (pinfunction "S_2") (pintype "passive"))
    )
    (net (code "49") (name "Net-(OK1-A)") (class "Default")
      (node (ref "OK1") (pin "1") (pinfunction "A_1") (pintype "passive"))
      (node (ref "R1") (pin "2") (pinfunction "2_2") (pintype "passive"))
    )
    (net (code "50") (name "Net-(OK1-COL)") (class "Default")
      (node (ref "OK1") (pin "4") (pinfunction "COL_4") (pintype "passive"))
      (node (ref "R3") (pin "1") (pinfunction "1_1") (pintype "passive"))
    )
    (net (code "51") (name "Net-(OK1-EMIT)") (class "Default")
      (node (ref "OK1") (pin "3") (pinfunction "EMIT_3") (pintype "passive"))
      (node (ref "X1") (pin "P$1") (pinfunction "1_P$1") (pintype "passive"))
    )
    (net (code "52") (name "Net-(OK2-A)") (class "Default")
      (node (ref "OK2") (pin "1") (pinfunction "A_1") (pintype "passive"))
      (node (ref "R2") (pin "1") (pinfunction "1_1") (pintype "passive"))
    )
    (net (code "53") (name "Net-(OK2-EMIT)") (class "Default")
      (node (ref "OK2") (pin "3") (pinfunction "EMIT_3") (pintype "passive"))
      (node (ref "R4") (pin "2") (pinfunction "2_2") (pintype "passive"))
      (node (ref "R5") (pin "2") (pinfunction "2_2") (pintype "passive"))
    )
    (net (code "54") (name "Net-(OK3-A)") (class "Default")
      (node (ref "OK3") (pin "1") (pinfunction "A_1") (pintype "passive"))
      (node (ref "R7") (pin "2") (pinfunction "2_2") (pintype "passive"))
    )
    (net (code "55") (name "Net-(OK3-COL)") (class "Default")
      (node (ref "OK3") (pin "4") (pinfunction "COL_4") (pintype "passive"))
      (node (ref "R9") (pin "1") (pinfunction "1_1") (pintype "passive"))
    )
    (net (code "56") (name "Net-(OK3-EMIT)") (class "Default")
      (node (ref "OK3") (pin "3") (pinfunction "EMIT_3") (pintype "passive"))
      (node (ref "X2") (pin "P$1") (pinfunction "1_P$1") (pintype "passive"))
    )
    (net (code "57") (name "Net-(OK4-A)") (class "Default")
      (node (ref "OK4") (pin "1") (pinfunction "A_1") (pintype "passive"))
      (node (ref "R8") (pin "1") (pinfunction "1_1") (pintype "passive"))
    )
    (net (code "58") (name "Net-(OK4-EMIT)") (class "Default")
      (node (ref "OK4") (pin "3") (pinfunction "EMIT_3") (pintype "passive"))
      (node (ref "R10") (pin "2") (pinfunction "2_2") (pintype "passive"))
      (node (ref "R11") (pin "2") (pinfunction "2_2") (pintype "passive"))
    )
    (net (code "59") (name "Net-(OK5-A)") (class "Default")
      (node (ref "OK5") (pin "1") (pinfunction "A_1") (pintype "passive"))
      (node (ref "R12") (pin "2") (pinfunction "2_2") (pintype "passive"))
    )
    (net (code "60") (name "Net-(OK5-COL)") (class "Default")
      (node (ref "OK5") (pin "4") (pinfunction "COL_4") (pintype "passive"))
      (node (ref "R16") (pin "1") (pinfunction "1_1") (pintype "passive"))
    )
    (net (code "61") (name "Net-(OK5-EMIT)") (class "Default")
      (node (ref "OK5") (pin "3") (pinfunction "EMIT_3") (pintype "passive"))
      (node (ref "X3") (pin "P$1") (pinfunction "1_P$1") (pintype "passive"))
    )
    (net (code "62") (name "Net-(OK6-A)") (class "Default")
      (node (ref "OK6") (pin "1") (pinfunction "A_1") (pintype "passive"))
      (node (ref "R13") (pin "2") (pinfunction "2_2") (pintype "passive"))
    )
    (net (code "63") (name "Net-(OK6-COL)") (class "Default")
      (node (ref "OK6") (pin "4") (pinfunction "COL_4") (pintype "passive"))
      (node (ref "R17") (pin "1") (pinfunction "1_1") (pintype "passive"))
    )
    (net (code "64") (name "Net-(OK6-EMIT)") (class "Default")
      (node (ref "OK6") (pin "3") (pinfunction "EMIT_3") (pintype "passive"))
      (node (ref "X3") (pin "P$3") (pinfunction "3_P$3") (pintype "passive"))
    )
    (net (code "65") (name "Net-(OK7-A)") (class "Default")
      (node (ref "OK7") (pin "1") (pinfunction "A_1") (pintype "passive"))
      (node (ref "R14") (pin "2") (pinfunction "2_2") (pintype "passive"))
    )
    (net (code "66") (name "Net-(OK7-COL)") (class "Default")
      (node (ref "OK7") (pin "4") (pinfunction "COL_4") (pintype "passive"))
      (node (ref "R18") (pin "1") (pinfunction "1_1") (pintype "passive"))
    )
    (net (code "67") (name "Net-(OK7-EMIT)") (class "Default")
      (node (ref "OK7") (pin "3") (pinfunction "EMIT_3") (pintype "passive"))
      (node (ref "X3") (pin "P$5") (pinfunction "5_P$5") (pintype "passive"))
    )
    (net (code "68") (name "Net-(OK8-A)") (class "Default")
      (node (ref "OK8") (pin "1") (pinfunction "A_1") (pintype "passive"))
      (node (ref "R15") (pin "1") (pinfunction "1_1") (pintype "passive"))
    )
    (net (code "69") (name "Net-(OK8-COL)") (class "Default")
      (node (ref "OK8") (pin "4") (pinfunction "COL_4") (pintype "passive"))
      (node (ref "Q5") (pin "1") (pinfunction "G_1") (pintype "passive"))
      (node (ref "R19") (pin "2") (pinfunction "2_2") (pintype "passive"))
    )
    (net (code "70") (name "Net-(OK9-A)") (class "Default")
      (node (ref "OK9") (pin "1") (pinfunction "A_1") (pintype "passive"))
      (node (ref "R20") (pin "2") (pinfunction "2_2") (pintype "passive"))
    )
    (net (code "71") (name "Net-(OK9-COL)") (class "Default")
      (node (ref "OK9") (pin "4") (pinfunction "COL_4") (pintype "passive"))
      (node (ref "R24") (pin "1") (pinfunction "1_1") (pintype "passive"))
    )
    (net (code "72") (name "Net-(OK9-EMIT)") (class "Default")
      (node (ref "OK9") (pin "3") (pinfunction "EMIT_3") (pintype "passive"))
      (node (ref "X5") (pin "P$1") (pinfunction "1_P$1") (pintype "passive"))
    )
    (net (code "73") (name "Net-(OK10-A)") (class "Default")
      (node (ref "OK10") (pin "1") (pinfunction "A_1") (pintype "passive"))
      (node (ref "R21") (pin "2") (pinfunction "2_2") (pintype "passive"))
    )
    (net (code "74") (name "Net-(OK10-COL)") (class "Default")
      (node (ref "OK10") (pin "4") (pinfunction "COL_4") (pintype "passive"))
      (node (ref "R25") (pin "1") (pinfunction "1_1") (pintype "passive"))
    )
    (net (code "75") (name "Net-(OK10-EMIT)") (class "Default")
      (node (ref "OK10") (pin "3") (pinfunction "EMIT_3") (pintype "passive"))
      (node (ref "X5") (pin "P$3") (pinfunction "3_P$3") (pintype "passive"))
    )
    (net (code "76") (name "Net-(OK11-A)") (class "Default")
      (node (ref "OK11") (pin "1") (pinfunction "A_1") (pintype "passive"))
      (node (ref "R22") (pin "2") (pinfunction "2_2") (pintype "passive"))
    )
    (net (code "77") (name "Net-(OK11-COL)") (class "Default")
      (node (ref "OK11") (pin "4") (pinfunction "COL_4") (pintype "passive"))
      (node (ref "R26") (pin "1") (pinfunction "1_1") (pintype "passive"))
    )
    (net (code "78") (name "Net-(OK11-EMIT)") (class "Default")
      (node (ref "OK11") (pin "3") (pinfunction "EMIT_3") (pintype "passive"))
      (node (ref "X5") (pin "P$5") (pinfunction "5_P$5") (pintype "passive"))
    )
    (net (code "79") (name "Net-(OK12-A)") (class "Default")
      (node (ref "OK12") (pin "1") (pinfunction "A_1") (pintype "passive"))
      (node (ref "R23") (pin "1") (pinfunction "1_1") (pintype "passive"))
    )
    (net (code "80") (name "Net-(OK12-COL)") (class "Default")
      (node (ref "OK12") (pin "4") (pinfunction "COL_4") (pintype "passive"))
      (node (ref "Q4") (pin "1") (pinfunction "G_1") (pintype "passive"))
      (node (ref "R27") (pin "2") (pinfunction "2_2") (pintype "passive"))
    )
    (net (code "81") (name "Net-(OK13-A)") (class "Default")
      (node (ref "OK13") (pin "1") (pinfunction "A_1") (pintype "passive"))
      (node (ref "R32") (pin "2") (pinfunction "2_2") (pintype "passive"))
    )
    (net (code "82") (name "Net-(OK13-COL)") (class "Default")
      (node (ref "OK13") (pin "4") (pinfunction "COL_4") (pintype "passive"))
      (node (ref "R36") (pin "1") (pinfunction "1_1") (pintype "passive"))
    )
    (net (code "83") (name "Net-(OK13-EMIT)") (class "Default")
      (node (ref "OK13") (pin "3") (pinfunction "EMIT_3") (pintype "passive"))
      (node (ref "X7") (pin "P$1") (pinfunction "1_P$1") (pintype "passive"))
    )
    (net (code "84") (name "Net-(OK14-A)") (class "Default")
      (node (ref "OK14") (pin "1") (pinfunction "A_1") (pintype "passive"))
      (node (ref "R33") (pin "1") (pinfunction "1_1") (pintype "passive"))
    )
    (net (code "85") (name "Net-(OK14-COL)") (class "Default")
      (node (ref "OK14") (pin "4") (pinfunction "COL_4") (pintype "passive"))
      (node (ref "Q3") (pin "1") (pinfunction "G_1") (pintype "passive"))
      (node (ref "R37") (pin "2") (pinfunction "2_2") (pintype "passive"))
    )
    (net (code "86") (name "Net-(OK15-A)") (class "Default")
      (node (ref "OK15") (pin "1") (pinfunction "A_1") (pintype "passive"))
      (node (ref "R38") (pin "2") (pinfunction "2_2") (pintype "passive"))
    )
    (net (code "87") (name "Net-(OK15-COL)") (class "Default")
      (node (ref "OK15") (pin "4") (pinfunction "COL_4") (pintype "passive"))
      (node (ref "R34") (pin "1") (pinfunction "1_1") (pintype "passive"))
    )
    (net (code "88") (name "Net-(OK16-A)") (class "Default")
      (node (ref "OK16") (pin "1") (pinfunction "A_1") (pintype "passive"))
      (node (ref "R35") (pin "2") (pinfunction "2_2") (pintype "passive"))
    )
    (net (code "89") (name "Net-(OK16-COL)") (class "Default")
      (node (ref "OK16") (pin "4") (pinfunction "COL_4") (pintype "passive"))
      (node (ref "Q2") (pin "1") (pinfunction "G_1") (pintype "passive"))
      (node (ref "R39") (pin "1") (pinfunction "1_1") (pintype "passive"))
    )
    (net (code "90") (name "Net-(Q1-G)") (class "Default")
      (node (ref "Q1") (pin "1") (pinfunction "G_1") (pintype "passive"))
      (node (ref "R6") (pin "2") (pinfunction "2_2") (pintype "passive"))
    )
    (net (code "91") (name "Net-(Q3-D)") (class "Default")
      (node (ref "Q3") (pin "3") (pinfunction "D_3") (pintype "passive"))
      (node (ref "R44") (pin "2") (pinfunction "2_2") (pintype "passive"))
      (node (ref "X8") (pin "P$1") (pinfunction "1_P$1") (pintype "passive"))
    )
    (net (code "92") (name "Net-(Q3-S)") (class "Default")
      (node (ref "Q3") (pin "2") (pinfunction "S_2") (pintype "passive"))
      (node (ref "R37") (pin "1") (pinfunction "1_1") (pintype "passive"))
      (node (ref "X8") (pin "P$2") (pinfunction "2_P$2") (pintype "passive"))
    )
    (net (code "93") (name "Net-(Q4-D)") (class "Default")
      (node (ref "Q4") (pin "3") (pinfunction "D_3") (pintype "passive"))
      (node (ref "R45") (pin "2") (pinfunction "2_2") (pintype "passive"))
      (node (ref "X6") (pin "P$1") (pinfunction "1_P$1") (pintype "passive"))
    )
    (net (code "94") (name "Net-(Q4-S)") (class "Default")
      (node (ref "Q4") (pin "2") (pinfunction "S_2") (pintype "passive"))
      (node (ref "R27") (pin "1") (pinfunction "1_1") (pintype "passive"))
      (node (ref "X6") (pin "P$2") (pinfunction "2_P$2") (pintype "passive"))
    )
    (net (code "95") (name "Net-(Q5-D)") (class "Default")
      (node (ref "Q5") (pin "3") (pinfunction "D_3") (pintype "passive"))
      (node (ref "R46") (pin "2") (pinfunction "2_2") (pintype "passive"))
      (node (ref "X4") (pin "P$1") (pinfunction "1_P$1") (pintype "passive"))
    )
    (net (code "96") (name "Net-(Q5-S)") (class "Default")
      (node (ref "Q5") (pin "2") (pinfunction "S_2") (pintype "passive"))
      (node (ref "R19") (pin "1") (pinfunction "1_1") (pintype "passive"))
      (node (ref "X4") (pin "P$2") (pinfunction "2_P$2") (pintype "passive"))
    )
    (net (code "97") (name "Net-(Q6-D)") (class "Default")
      (node (ref "Q6") (pin "3") (pinfunction "D_3") (pintype "passive"))
      (node (ref "X2") (pin "P$4") (pinfunction "4_P$4") (pintype "passive"))
    )
    (net (code "98") (name "Net-(Q6-G)") (class "Default")
      (node (ref "Q6") (pin "1") (pinfunction "G_1") (pintype "passive"))
      (node (ref "R10") (pin "1") (pinfunction "1_1") (pintype "passive"))
    )
    (net (code "99") (name "Net-(Q7-D)") (class "Default")
      (node (ref "Q7") (pin "3") (pinfunction "D_3") (pintype "passive"))
      (node (ref "X1") (pin "P$4") (pinfunction "4_P$4") (pintype "passive"))
    )
    (net (code "100") (name "Net-(Q7-G)") (class "Default")
      (node (ref "Q7") (pin "1") (pinfunction "G_1") (pintype "passive"))
      (node (ref "R4") (pin "1") (pinfunction "1_1") (pintype "passive"))
    )
    (net (code "101") (name "Net-(X3-4)") (class "Default")
      (node (ref "R46") (pin "1") (pinfunction "1_1") (pintype "passive"))
      (node (ref "X3") (pin "P$4") (pinfunction "4_P$4") (pintype "passive"))
    )
    (net (code "102") (name "Net-(X5-4)") (class "Default")
      (node (ref "R45") (pin "1") (pinfunction "1_1") (pintype "passive"))
      (node (ref "X5") (pin "P$4") (pinfunction "4_P$4") (pintype "passive"))
    )
    (net (code "103") (name "Net-(X7-4)") (class "Default")
      (node (ref "R44") (pin "1") (pinfunction "1_1") (pintype "passive"))
      (node (ref "X7") (pin "P$4") (pinfunction "4_P$4") (pintype "passive"))
    )
    (net (code "104") (name "unconnected-(IC3-3V3_EN-PadP$37)") (class "Default")
      (node (ref "IC3") (pin "P$37") (pinfunction "3V3_EN_P$37") (pintype "input"))
    )
    (net (code "105") (name "unconnected-(IC3-ADC_REF-PadP$35)") (class "Default")
      (node (ref "IC3") (pin "P$35") (pinfunction "ADC_REF_P$35") (pintype "input"))
    )
    (net (code "106") (name "unconnected-(IC3-RUN-PadP$30)") (class "Default")
      (node (ref "IC3") (pin "P$30") (pinfunction "RUN_P$30") (pintype "input"))
    )
    (net (code "107") (name "unconnected-(IC3-SWCLK-PadP$41)") (class "Default")
      (node (ref "IC3") (pin "P$41") (pinfunction "SWCLK_P$41") (pintype "input"))
    )
    (net (code "108") (name "unconnected-(IC3-SWDIO-PadP$43)") (class "Default")
      (node (ref "IC3") (pin "P$43") (pinfunction "SWDIO_P$43") (pintype "bidirectional"))
    )
    (net (code "109") (name "unconnected-(X1-3-PadP$3)") (class "Default")
      (node (ref "X1") (pin "P$3") (pinfunction "3_P$3") (pintype "passive"))
    )
    (net (code "110") (name "unconnected-(X1-5-PadP$5)") (class "Default")
      (node (ref "X1") (pin "P$5") (pinfunction "5_P$5") (pintype "passive"))
    )
    (net (code "111") (name "unconnected-(X2-3-PadP$3)") (class "Default")
      (node (ref "X2") (pin "P$3") (pinfunction "3_P$3") (pintype "passive"))
    )
    (net (code "112") (name "unconnected-(X2-5-PadP$5)") (class "Default")
      (node (ref "X2") (pin "P$5") (pinfunction "5_P$5") (pintype "passive"))
    )
    (net (code "113") (name "unconnected-(X7-3-PadP$3)") (class "Default")
      (node (ref "X7") (pin "P$3") (pinfunction "3_P$3") (pintype "passive"))
    )
    (net (code "114") (name "unconnected-(X7-5-PadP$5)") (class "Default")
      (node (ref "X7") (pin "P$5") (pinfunction "5_P$5") (pintype "passive"))
    )
  )
)
